# BatCollector.net
KiCad netlist of a schematic drawn in Altium Designer
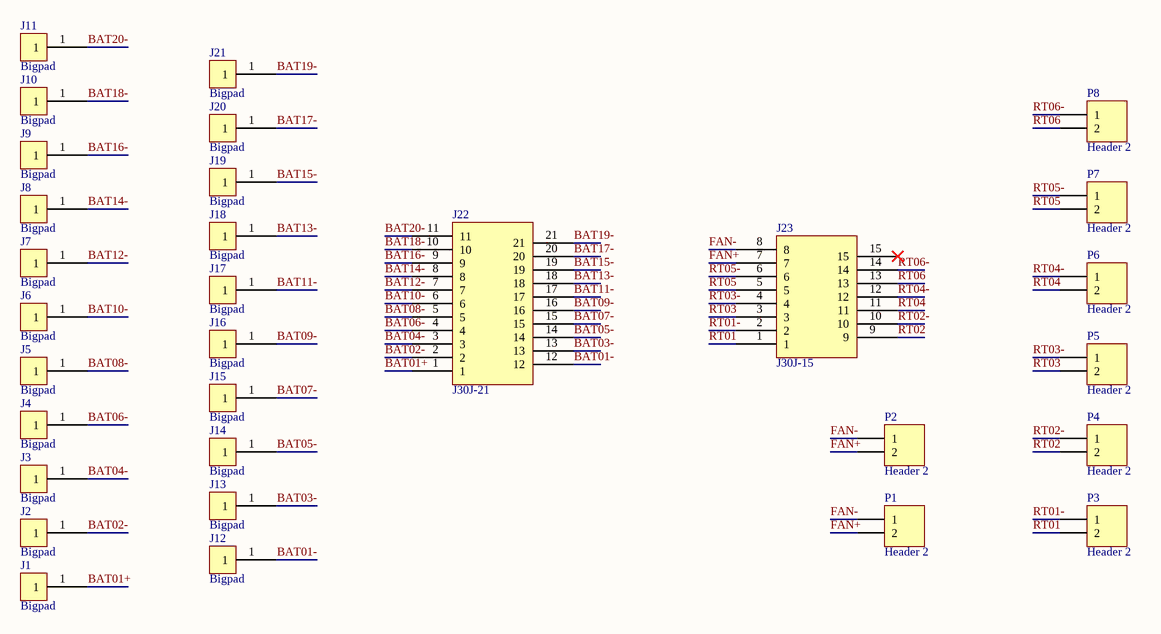
[diagram p0: BatCollector.SchDoc]

(export (version "E")
  (design (tool "Eeschema 10.0.6"))
  (components
    (comp (ref "J1")
      (value "Bigpad")
      (footprint "Bigpad")
      (libsource (lib "自动化研究所集成库20170403") (part "Bigpad"))
    )
    (comp (ref "J2")
      (value "Bigpad")
      (footprint "Bigpad")
      (libsource (lib "自动化研究所集成库20170403") (part "Bigpad"))
    )
    (comp (ref "J3")
      (value "Bigpad")
      (footprint "Bigpad")
      (libsource (lib "自动化研究所集成库20170403") (part "Bigpad"))
    )
    (comp (ref "J4")
      (value "Bigpad")
      (footprint "Bigpad")
      (libsource (lib "自动化研究所集成库20170403") (part "Bigpad"))
    )
    (comp (ref "J5")
      (value "Bigpad")
      (footprint "Bigpad")
      (libsource (lib "自动化研究所集成库20170403") (part "Bigpad"))
    )
    (comp (ref "J6")
      (value "Bigpad")
      (footprint "Bigpad")
      (libsource (lib "自动化研究所集成库20170403") (part "Bigpad"))
    )
    (comp (ref "J7")
      (value "Bigpad")
      (footprint "Bigpad")
      (libsource (lib "自动化研究所集成库20170403") (part "Bigpad"))
    )
    (comp (ref "J8")
      (value "Bigpad")
      (footprint "Bigpad")
      (libsource (lib "自动化研究所集成库20170403") (part "Bigpad"))
    )
    (comp (ref "J9")
      (value "Bigpad")
      (footprint "Bigpad")
      (libsource (lib "自动化研究所集成库20170403") (part "Bigpad"))
    )
    (comp (ref "J10")
      (value "Bigpad")
      (footprint "Bigpad")
      (libsource (lib "自动化研究所集成库20170403") (part "Bigpad"))
    )
    (comp (ref "J11")
      (value "Bigpad")
      (footprint "Bigpad")
      (libsource (lib "自动化研究所集成库20170403") (part "Bigpad"))
    )
    (comp (ref "J12")
      (value "Bigpad")
      (footprint "Bigpad")
      (libsource (lib "自动化研究所集成库20170403") (part "Bigpad"))
    )
    (comp (ref "J13")
      (value "Bigpad")
      (footprint "Bigpad")
      (libsource (lib "自动化研究所集成库20170403") (part "Bigpad"))
    )
    (comp (ref "J14")
      (value "Bigpad")
      (footprint "Bigpad")
      (libsource (lib "自动化研究所集成库20170403") (part "Bigpad"))
    )
    (comp (ref "J15")
      (value "Bigpad")
      (footprint "Bigpad")
      (libsource (lib "自动化研究所集成库20170403") (part "Bigpad"))
    )
    (comp (ref "J16")
      (value "Bigpad")
      (footprint "Bigpad")
      (libsource (lib "自动化研究所集成库20170403") (part "Bigpad"))
    )
    (comp (ref "J17")
      (value "Bigpad")
      (footprint "Bigpad")
      (libsource (lib "自动化研究所集成库20170403") (part "Bigpad"))
    )
    (comp (ref "J18")
      (value "Bigpad")
      (footprint "Bigpad")
      (libsource (lib "自动化研究所集成库20170403") (part "Bigpad"))
    )
    (comp (ref "J19")
      (value "Bigpad")
      (footprint "Bigpad")
      (libsource (lib "自动化研究所集成库20170403") (part "Bigpad"))
    )
    (comp (ref "J20")
      (value "Bigpad")
      (footprint "Bigpad")
      (libsource (lib "自动化研究所集成库20170403") (part "Bigpad"))
    )
    (comp (ref "J21")
      (value "Bigpad")
      (footprint "Bigpad")
      (libsource (lib "自动化研究所集成库20170403") (part "Bigpad"))
    )
    (comp (ref "J22")
      (value "J30J-21")
      (footprint "J30J-21")
      (libsource (lib "自动化研究所集成库20170403") (part "J30J-21"))
    )
    (comp (ref "J23")
      (value "J30J-15")
      (footprint "J30J-15")
      (libsource (lib "自动化研究所集成库20170403") (part "J30J-15"))
    )
    (comp (ref "P1")
      (value "Header 2")
      (footprint "HDR1X2")
      (description "Header, 2-Pin")
      (fields (field (name "PUBLISHER") "Altium Limited"))
      (libsource (lib "Miscellaneous Connectors") (part "Header 2"))
    )
    (comp (ref "P2")
      (value "Header 2")
      (footprint "HDR1X2")
      (description "Header, 2-Pin")
      (fields (field (name "PUBLISHER") "Altium Limited"))
      (libsource (lib "Miscellaneous Connectors") (part "Header 2"))
    )
    (comp (ref "P3")
      (value "Header 2")
      (footprint "HDR1X2")
      (description "Header, 2-Pin")
      (fields (field (name "PUBLISHER") "Altium Limited"))
      (libsource (lib "Miscellaneous Connectors") (part "Header 2"))
    )
    (comp (ref "P4")
      (value "Header 2")
      (footprint "HDR1X2")
      (description "Header, 2-Pin")
      (fields (field (name "PUBLISHER") "Altium Limited"))
      (libsource (lib "Miscellaneous Connectors") (part "Header 2"))
    )
    (comp (ref "P5")
      (value "Header 2")
      (footprint "HDR1X2")
      (description "Header, 2-Pin")
      (fields (field (name "PUBLISHER") "Altium Limited"))
      (libsource (lib "Miscellaneous Connectors") (part "Header 2"))
    )
    (comp (ref "P6")
      (value "Header 2")
      (footprint "HDR1X2")
      (description "Header, 2-Pin")
      (fields (field (name "PUBLISHER") "Altium Limited"))
      (libsource (lib "Miscellaneous Connectors") (part "Header 2"))
    )
    (comp (ref "P7")
      (value "Header 2")
      (footprint "HDR1X2")
      (description "Header, 2-Pin")
      (fields (field (name "PUBLISHER") "Altium Limited"))
      (libsource (lib "Miscellaneous Connectors") (part "Header 2"))
    )
    (comp (ref "P8")
      (value "Header 2")
      (footprint "HDR1X2")
      (description "Header, 2-Pin")
      (fields (field (name "PUBLISHER") "Altium Limited"))
      (libsource (lib "Miscellaneous Connectors") (part "Header 2"))
    )
  )
  (nets
    (net (code "1") (name "/BAT01+") (class "Default")
      (node (ref "J1") (pin "1") (pinfunction "1_1") (pintype "passive"))
      (node (ref "J22") (pin "1") (pinfunction "1_1") (pintype "passive"))
    )
    (net (code "2") (name "/BAT01-") (class "Default")
      (node (ref "J12") (pin "1") (pinfunction "1_1") (pintype "passive"))
      (node (ref "J22") (pin "12") (pinfunction "12_12") (pintype "passive"))
    )
    (net (code "3") (name "/BAT02-") (class "Default")
      (node (ref "J2") (pin "1") (pinfunction "1_1") (pintype "passive"))
      (node (ref "J22") (pin "2") (pinfunction "2_2") (pintype "passive"))
    )
    (net (code "4") (name "/BAT03-") (class "Default")
      (node (ref "J13") (pin "1") (pinfunction "1_1") (pintype "passive"))
      (node (ref "J22") (pin "13") (pinfunction "13_13") (pintype "passive"))
    )
    (net (code "5") (name "/BAT04-") (class "Default")
      (node (ref "J22") (pin "3") (pinfunction "3_3") (pintype "passive"))
      (node (ref "J3") (pin "1") (pinfunction "1_1") (pintype "passive"))
    )
    (net (code "6") (name "/BAT05-") (class "Default")
      (node (ref "J14") (pin "1") (pinfunction "1_1") (pintype "passive"))
      (node (ref "J22") (pin "14") (pinfunction "14_14") (pintype "passive"))
    )
    (net (code "7") (name "/BAT06-") (class "Default")
      (node (ref "J22") (pin "4") (pinfunction "4_4") (pintype "passive"))
      (node (ref "J4") (pin "1") (pinfunction "1_1") (pintype "passive"))
    )
    (net (code "8") (name "/BAT07-") (class "Default")
      (node (ref "J15") (pin "1") (pinfunction "1_1") (pintype "passive"))
      (node (ref "J22") (pin "15") (pinfunction "15_15") (pintype "passive"))
    )
    (net (code "9") (name "/BAT08-") (class "Default")
      (node (ref "J22") (pin "5") (pinfunction "5_5") (pintype "passive"))
      (node (ref "J5") (pin "1") (pinfunction "1_1") (pintype "passive"))
    )
    (net (code "10") (name "/BAT09-") (class "Default")
      (node (ref "J16") (pin "1") (pinfunction "1_1") (pintype "passive"))
      (node (ref "J22") (pin "16") (pinfunction "16_16") (pintype "passive"))
    )
    (net (code "11") (name "/BAT10-") (class "Default")
      (node (ref "J22") (pin "6") (pinfunction "6_6") (pintype "passive"))
      (node (ref "J6") (pin "1") (pinfunction "1_1") (pintype "passive"))
    )
    (net (code "12") (name "/BAT11-") (class "Default")
      (node (ref "J17") (pin "1") (pinfunction "1_1") (pintype "passive"))
      (node (ref "J22") (pin "17") (pinfunction "17_17") (pintype "passive"))
    )
    (net (code "13") (name "/BAT12-") (class "Default")
      (node (ref "J22") (pin "7") (pinfunction "7_7") (pintype "passive"))
      (node (ref "J7") (pin "1") (pinfunction "1_1") (pintype "passive"))
    )
    (net (code "14") (name "/BAT13-") (class "Default")
      (node (ref "J18") (pin "1") (pinfunction "1_1") (pintype "passive"))
      (node (ref "J22") (pin "18") (pinfunction "18_18") (pintype "passive"))
    )
    (net (code "15") (name "/BAT14-") (class "Default")
      (node (ref "J22") (pin "8") (pinfunction "8_8") (pintype "passive"))
      (node (ref "J8") (pin "1") (pinfunction "1_1") (pintype "passive"))
    )
    (net (code "16") (name "/BAT15-") (class "Default")
      (node (ref "J19") (pin "1") (pinfunction "1_1") (pintype "passive"))
      (node (ref "J22") (pin "19") (pinfunction "19_19") (pintype "passive"))
    )
    (net (code "17") (name "/BAT16-") (class "Default")
      (node (ref "J22") (pin "9") (pinfunction "9_9") (pintype "passive"))
      (node (ref "J9") (pin "1") (pinfunction "1_1") (pintype "passive"))
    )
    (net (code "18") (name "/BAT17-") (class "Default")
      (node (ref "J20") (pin "1") (pinfunction "1_1") (pintype "passive"))
      (node (ref "J22") (pin "20") (pinfunction "20_20") (pintype "passive"))
    )
    (net (code "19") (name "/BAT18-") (class "Default")
      (node (ref "J10") (pin "1") (pinfunction "1_1") (pintype "passive"))
      (node (ref "J22") (pin "10") (pinfunction "10_10") (pintype "passive"))
    )
    (net (code "20") (name "/BAT19-") (class "Default")
      (node (ref "J21") (pin "1") (pinfunction "1_1") (pintype "passive"))
      (node (ref "J22") (pin "21") (pinfunction "21_21") (pintype "passive"))
    )
    (net (code "21") (name "/BAT20-") (class "Default")
      (node (ref "J11") (pin "1") (pinfunction "1_1") (pintype "passive"))
      (node (ref "J22") (pin "11") (pinfunction "11_11") (pintype "passive"))
    )
    (net (code "22") (name "/FAN+") (class "Default")
      (node (ref "J23") (pin "7") (pinfunction "7_7") (pintype "passive"))
      (node (ref "P1") (pin "2") (pinfunction "2_2") (pintype "passive"))
      (node (ref "P2") (pin "2") (pinfunction "2_2") (pintype "passive"))
    )
    (net (code "23") (name "/FAN-") (class "Default")
      (node (ref "J23") (pin "8") (pinfunction "8_8") (pintype "passive"))
      (node (ref "P1") (pin "1") (pinfunction "1_1") (pintype "passive"))
      (node (ref "P2") (pin "1") (pinfunction "1_1") (pintype "passive"))
    )
    (net (code "24") (name "/RT01") (class "Default")
      (node (ref "J23") (pin "1") (pinfunction "1_1") (pintype "passive"))
      (node (ref "P3") (pin "2") (pinfunction "2_2") (pintype "passive"))
    )
    (net (code "25") (name "/RT01-") (class "Default")
      (node (ref "J23") (pin "2") (pinfunction "2_2") (pintype "passive"))
      (node (ref "P3") (pin "1") (pinfunction "1_1") (pintype "passive"))
    )
    (net (code "26") (name "/RT02") (class "Default")
      (node (ref "J23") (pin "9") (pinfunction "9_9") (pintype "passive"))
      (node (ref "P4") (pin "2") (pinfunction "2_2") (pintype "passive"))
    )
    (net (code "27") (name "/RT02-") (class "Default")
      (node (ref "J23") (pin "10") (pinfunction "10_10") (pintype "passive"))
      (node (ref "P4") (pin "1") (pinfunction "1_1") (pintype "passive"))
    )
    (net (code "28") (name "/RT03") (class "Default")
      (node (ref "J23") (pin "3") (pinfunction "3_3") (pintype "passive"))
      (node (ref "P5") (pin "2") (pinfunction "2_2") (pintype "passive"))
    )
    (net (code "29") (name "/RT03-") (class "Default")
      (node (ref "J23") (pin "4") (pinfunction "4_4") (pintype "passive"))
      (node (ref "P5") (pin "1") (pinfunction "1_1") (pintype "passive"))
    )
    (net (code "30") (name "/RT04") (class "Default")
      (node (ref "J23") (pin "11") (pinfunction "11_11") (pintype "passive"))
      (node (ref "P6") (pin "2") (pinfunction "2_2") (pintype "passive"))
    )
    (net (code "31") (name "/RT04-") (class "Default")
      (node (ref "J23") (pin "12") (pinfunction "12_12") (pintype "passive"))
      (node (ref "P6") (pin "1") (pinfunction "1_1") (pintype "passive"))
    )
    (net (code "32") (name "/RT05") (class "Default")
      (node (ref "J23") (pin "5") (pinfunction "5_5") (pintype "passive"))
      (node (ref "P7") (pin "2") (pinfunction "2_2") (pintype "passive"))
    )
    (net (code "33") (name "/RT05-") (class "Default")
      (node (ref "J23") (pin "6") (pinfunction "6_6") (pintype "passive"))
      (node (ref "P7") (pin "1") (pinfunction "1_1") (pintype "passive"))
    )
    (net (code "34") (name "/RT06") (class "Default")
      (node (ref "J23") (pin "13") (pinfunction "13_13") (pintype "passive"))
      (node (ref "P8") (pin "2") (pinfunction "2_2") (pintype "passive"))
    )
    (net (code "35") (name "/RT06-") (class "Default")
      (node (ref "J23") (pin "14") (pinfunction "14_14") (pintype "passive"))
      (node (ref "P8") (pin "1") (pinfunction "1_1") (pintype "passive"))
    )
    (net (code "36") (name "unconnected-(J23-Pad15)") (class "Default")
      (node (ref "J23") (pin "15") (pinfunction "15_15") (pintype "passive+no_connect"))
    )
  )
)
